# fbri_flight.net
KiCad netlist of a schematic drawn in EAGLE
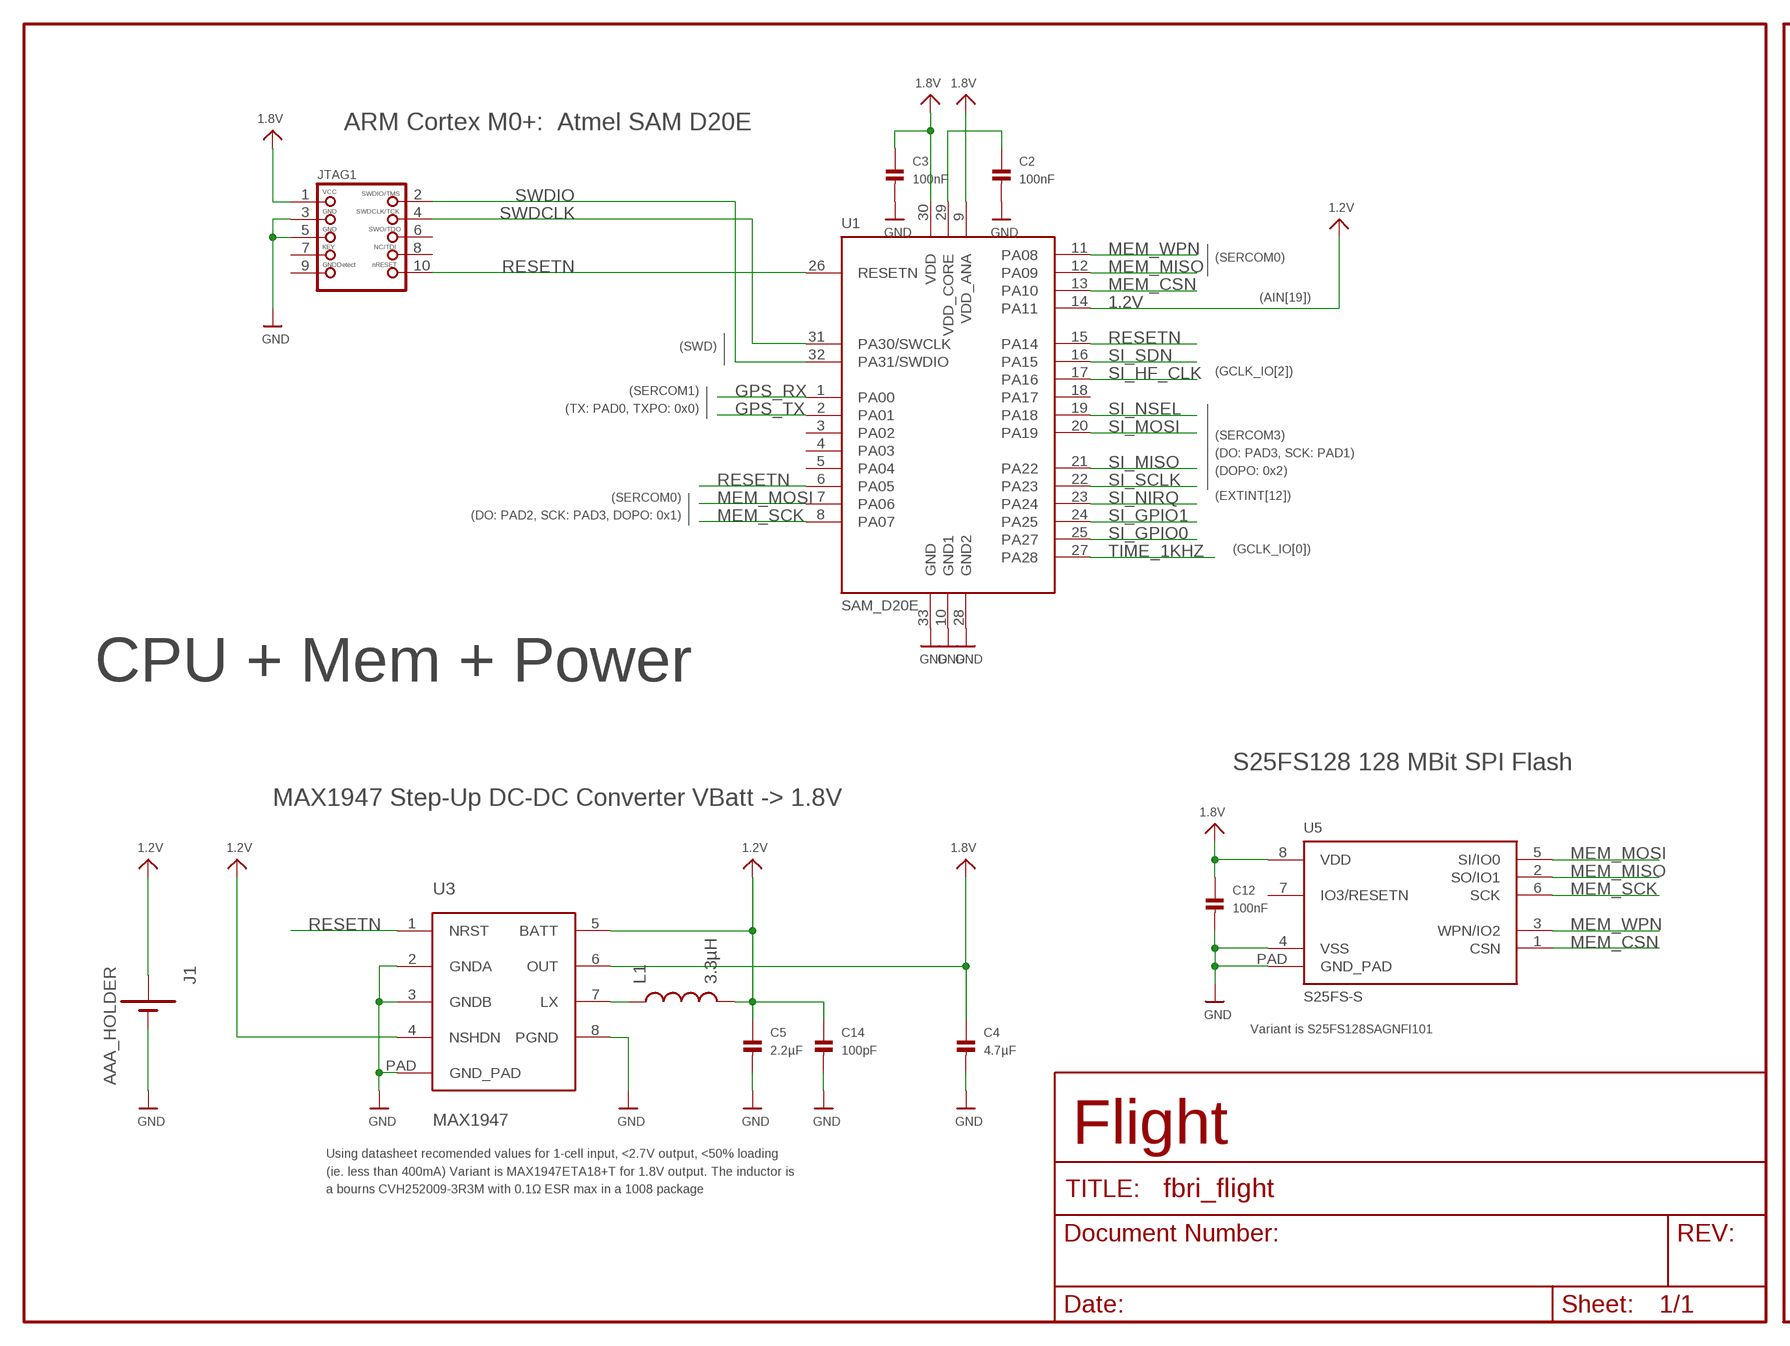
[diagram p0: schematic, sheet 1, part 1 of 2]
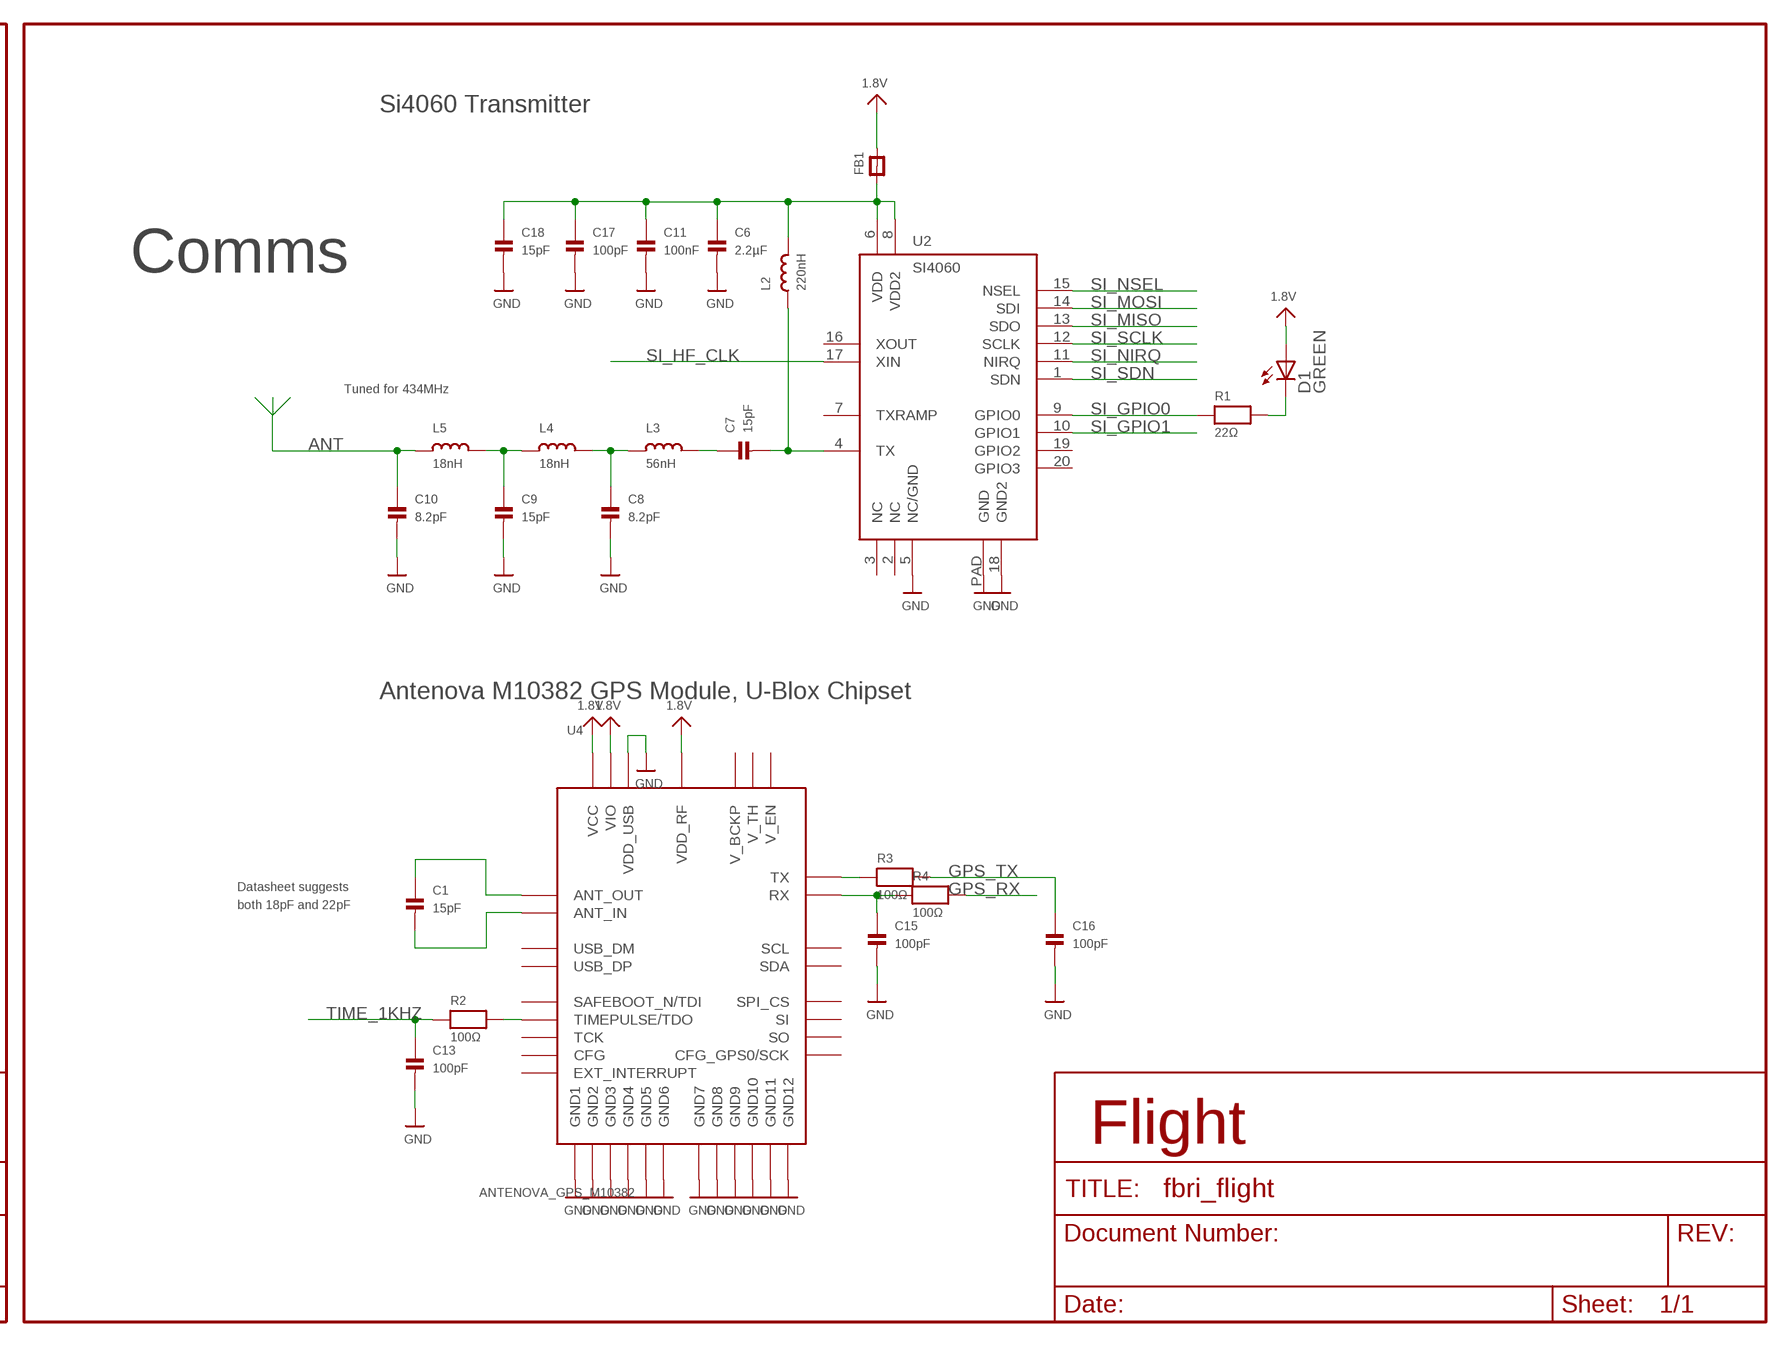
[diagram p1: schematic, sheet 1, part 2 of 2]

(export (version "E")
  (design (tool "Eeschema 10.0.6"))
  (components
    (comp (ref "C1")
      (value "15pF")
      (footprint "eagle-import:_0402")
      (libsource (lib "eagle-import") (part "CAP_CERAMIC_0402"))
    )
    (comp (ref "C2")
      (value "100nF")
      (footprint "eagle-import:_0402")
      (libsource (lib "eagle-import") (part "CAP_CERAMIC_0402"))
    )
    (comp (ref "C3")
      (value "100nF")
      (footprint "eagle-import:_0402")
      (libsource (lib "eagle-import") (part "CAP_CERAMIC_0402"))
    )
    (comp (ref "C4")
      (value "4.7µF")
      (footprint "eagle-import:_0402")
      (libsource (lib "eagle-import") (part "CAP_CERAMIC_0402"))
    )
    (comp (ref "C5")
      (value "2.2µF")
      (footprint "eagle-import:_0402")
      (libsource (lib "eagle-import") (part "CAP_CERAMIC_0402"))
    )
    (comp (ref "C6")
      (value "2.2µF")
      (footprint "eagle-import:_0402")
      (libsource (lib "eagle-import") (part "CAP_CERAMIC_0402"))
    )
    (comp (ref "C7")
      (value "15pF")
      (footprint "eagle-import:_0402")
      (libsource (lib "eagle-import") (part "CAP_CERAMIC_0402"))
    )
    (comp (ref "C8")
      (value "8.2pF")
      (footprint "eagle-import:_0402")
      (libsource (lib "eagle-import") (part "CAP_CERAMIC_0402"))
    )
    (comp (ref "C9")
      (value "15pF")
      (footprint "eagle-import:_0402")
      (libsource (lib "eagle-import") (part "CAP_CERAMIC_0402"))
    )
    (comp (ref "C10")
      (value "8.2pF")
      (footprint "eagle-import:_0402")
      (libsource (lib "eagle-import") (part "CAP_CERAMIC_0402"))
    )
    (comp (ref "C11")
      (value "100nF")
      (footprint "eagle-import:_0402")
      (libsource (lib "eagle-import") (part "CAP_CERAMIC_0402"))
    )
    (comp (ref "C12")
      (value "100nF")
      (footprint "eagle-import:_0402")
      (libsource (lib "eagle-import") (part "CAP_CERAMIC_0402"))
    )
    (comp (ref "C13")
      (value "100pF")
      (footprint "eagle-import:_0402")
      (libsource (lib "eagle-import") (part "CAP_CERAMIC_0402"))
    )
    (comp (ref "C14")
      (value "100pF")
      (footprint "eagle-import:_0402")
      (libsource (lib "eagle-import") (part "CAP_CERAMIC_0402"))
    )
    (comp (ref "C15")
      (value "100pF")
      (footprint "eagle-import:_0402")
      (libsource (lib "eagle-import") (part "CAP_CERAMIC_0402"))
    )
    (comp (ref "C16")
      (value "100pF")
      (footprint "eagle-import:_0402")
      (libsource (lib "eagle-import") (part "CAP_CERAMIC_0402"))
    )
    (comp (ref "C17")
      (value "100pF")
      (footprint "eagle-import:_0402")
      (libsource (lib "eagle-import") (part "CAP_CERAMIC_0402"))
    )
    (comp (ref "C18")
      (value "15pF")
      (footprint "eagle-import:_0402")
      (libsource (lib "eagle-import") (part "CAP_CERAMIC_0402"))
    )
    (comp (ref "D1")
      (value "GREEN")
      (footprint "eagle-import:CHIPLED_0603")
      (libsource (lib "eagle-import") (part "LEDCHIPLED_0603"))
    )
    (comp (ref "FB1")
      (value "FERRITE_0402")
      (footprint "eagle-import:_0402")
      (libsource (lib "eagle-import") (part "FERRITE_0402"))
    )
    (comp (ref "J1")
      (value "AAA_HOLDER")
      (footprint "eagle-import:AAA")
      (libsource (lib "eagle-import") (part "AAA_HOLDER"))
    )
    (comp (ref "JTAG1")
      (value "JTAG-CORTEXM3SMT")
      (footprint "eagle-import:2X05_1.27MM_SMT")
      (libsource (lib "eagle-import") (part "JTAG-CORTEXM3SMT"))
    )
    (comp (ref "L1")
      (value "3.3µH")
      (footprint "eagle-import:1007")
      (libsource (lib "eagle-import") (part "INDUCTOR1007"))
    )
    (comp (ref "L2")
      (value "220nH")
      (footprint "eagle-import:_0402")
      (libsource (lib "eagle-import") (part "INDUCTOR_0402"))
    )
    (comp (ref "L3")
      (value "56nH")
      (footprint "eagle-import:_0402")
      (libsource (lib "eagle-import") (part "INDUCTOR_0402"))
    )
    (comp (ref "L4")
      (value "18nH")
      (footprint "eagle-import:_0402")
      (libsource (lib "eagle-import") (part "INDUCTOR_0402"))
    )
    (comp (ref "L5")
      (value "18nH")
      (footprint "eagle-import:_0402")
      (libsource (lib "eagle-import") (part "INDUCTOR_0402"))
    )
    (comp (ref "R1")
      (value "22Ω")
      (footprint "eagle-import:_0402")
      (libsource (lib "eagle-import") (part "RESISTOR_0402"))
    )
    (comp (ref "R2")
      (value "100Ω")
      (footprint "eagle-import:_0402")
      (libsource (lib "eagle-import") (part "RESISTOR_0402"))
    )
    (comp (ref "R3")
      (value "100Ω")
      (footprint "eagle-import:_0402")
      (libsource (lib "eagle-import") (part "RESISTOR_0402"))
    )
    (comp (ref "R4")
      (value "100Ω")
      (footprint "eagle-import:_0402")
      (libsource (lib "eagle-import") (part "RESISTOR_0402"))
    )
    (comp (ref "U1")
      (value "SAM_D20E")
      (footprint "eagle-import:QFN32_5MM")
      (libsource (lib "eagle-import") (part "SAM_D20E"))
    )
    (comp (ref "U2")
      (value "SI4060")
      (footprint "eagle-import:QFN20")
      (libsource (lib "eagle-import") (part "SI4060"))
    )
    (comp (ref "U3")
      (value "MAX1947")
      (footprint "eagle-import:TDFN8")
      (libsource (lib "eagle-import") (part "MAX1947"))
    )
    (comp (ref "U4")
      (value "ANTENOVA_GPS_M10382")
      (footprint "eagle-import:ANTENOVA_GPS_M10382")
      (libsource (lib "eagle-import") (part "ANTENOVA_GPS_M10382"))
    )
    (comp (ref "U5")
      (value "S25FS-S")
      (footprint "eagle-import:WSON8")
      (libsource (lib "eagle-import") (part "S25FS-S"))
    )
  )
  (nets
    (net (code "1") (name "/ANT") (class "Default")
      (node (ref "C10") (pin "1") (pinfunction "P$1_1") (pintype "passive"))
      (node (ref "L5") (pin "1") (pinfunction "1_1") (pintype "passive"))
    )
    (net (code "2") (name "/GPS_RX") (class "Default")
      (node (ref "R4") (pin "2") (pinfunction "2_2") (pintype "passive"))
      (node (ref "U1") (pin "1") (pinfunction "PA00_1") (pintype "bidirectional"))
    )
    (net (code "3") (name "/GPS_TX") (class "Default")
      (node (ref "C16") (pin "1") (pinfunction "P$1_1") (pintype "passive"))
      (node (ref "R3") (pin "2") (pinfunction "2_2") (pintype "passive"))
      (node (ref "U1") (pin "2") (pinfunction "PA01_2") (pintype "bidirectional"))
    )
    (net (code "4") (name "/MEM_CSN") (class "Default")
      (node (ref "U1") (pin "13") (pinfunction "PA10_13") (pintype "bidirectional"))
      (node (ref "U5") (pin "1") (pinfunction "CSN_1") (pintype "input"))
    )
    (net (code "5") (name "/MEM_MISO") (class "Default")
      (node (ref "U1") (pin "12") (pinfunction "PA09_12") (pintype "bidirectional"))
      (node (ref "U5") (pin "2") (pinfunction "SO/IO1_2") (pintype "output"))
    )
    (net (code "6") (name "/MEM_MOSI") (class "Default")
      (node (ref "U1") (pin "7") (pinfunction "PA06_7") (pintype "bidirectional"))
      (node (ref "U5") (pin "5") (pinfunction "SI/IO0_5") (pintype "bidirectional"))
    )
    (net (code "7") (name "/MEM_SCK") (class "Default")
      (node (ref "U1") (pin "8") (pinfunction "PA07_8") (pintype "bidirectional"))
      (node (ref "U5") (pin "6") (pinfunction "SCK_6") (pintype "input"))
    )
    (net (code "8") (name "/MEM_WPN") (class "Default")
      (node (ref "U1") (pin "11") (pinfunction "PA08_11") (pintype "bidirectional"))
      (node (ref "U5") (pin "3") (pinfunction "WPN/IO2_3") (pintype "output"))
    )
    (net (code "9") (name "/RESETN") (class "Default")
      (node (ref "JTAG1") (pin "10") (pinfunction "10_10") (pintype "passive"))
      (node (ref "U1") (pin "15") (pinfunction "PA14_15") (pintype "bidirectional"))
      (node (ref "U1") (pin "26") (pinfunction "RESETN_26") (pintype "input"))
      (node (ref "U1") (pin "6") (pinfunction "PA05_6") (pintype "bidirectional"))
      (node (ref "U3") (pin "1") (pinfunction "NRST_1") (pintype "bidirectional"))
    )
    (net (code "10") (name "/SI_GPIO0") (class "Default")
      (node (ref "R1") (pin "1") (pinfunction "1_1") (pintype "passive"))
      (node (ref "U1") (pin "25") (pinfunction "PA27_25") (pintype "bidirectional"))
      (node (ref "U2") (pin "9") (pinfunction "GPIO0_9") (pintype "bidirectional"))
    )
    (net (code "11") (name "/SI_GPIO1") (class "Default")
      (node (ref "U1") (pin "24") (pinfunction "PA25_24") (pintype "bidirectional"))
      (node (ref "U2") (pin "10") (pinfunction "GPIO1_10") (pintype "bidirectional"))
    )
    (net (code "12") (name "/SI_HF_CLK") (class "Default")
      (node (ref "U1") (pin "17") (pinfunction "PA16_17") (pintype "bidirectional"))
      (node (ref "U2") (pin "17") (pinfunction "XIN_17") (pintype "input"))
    )
    (net (code "13") (name "/SI_MISO") (class "Default")
      (node (ref "U1") (pin "21") (pinfunction "PA22_21") (pintype "bidirectional"))
      (node (ref "U2") (pin "13") (pinfunction "SDO_13") (pintype "output"))
    )
    (net (code "14") (name "/SI_MOSI") (class "Default")
      (node (ref "U1") (pin "20") (pinfunction "PA19_20") (pintype "bidirectional"))
      (node (ref "U2") (pin "14") (pinfunction "SDI_14") (pintype "bidirectional"))
    )
    (net (code "15") (name "/SI_NIRQ") (class "Default")
      (node (ref "U1") (pin "23") (pinfunction "PA24_23") (pintype "bidirectional"))
      (node (ref "U2") (pin "11") (pinfunction "NIRQ_11") (pintype "output"))
    )
    (net (code "16") (name "/SI_NSEL") (class "Default")
      (node (ref "U1") (pin "19") (pinfunction "PA18_19") (pintype "bidirectional"))
      (node (ref "U2") (pin "15") (pinfunction "NSEL_15") (pintype "input"))
    )
    (net (code "17") (name "/SI_SCLK") (class "Default")
      (node (ref "U1") (pin "22") (pinfunction "PA23_22") (pintype "bidirectional"))
      (node (ref "U2") (pin "12") (pinfunction "SCLK_12") (pintype "input"))
    )
    (net (code "18") (name "/SI_SDN") (class "Default")
      (node (ref "U1") (pin "16") (pinfunction "PA15_16") (pintype "bidirectional"))
      (node (ref "U2") (pin "1") (pinfunction "SDN_1") (pintype "input"))
    )
    (net (code "19") (name "/SWDCLK") (class "Default")
      (node (ref "JTAG1") (pin "4") (pinfunction "4_4") (pintype "passive"))
      (node (ref "U1") (pin "31") (pinfunction "PA30/SWCLK_31") (pintype "bidirectional"))
    )
    (net (code "20") (name "/SWDIO") (class "Default")
      (node (ref "JTAG1") (pin "2") (pinfunction "2_2") (pintype "passive"))
      (node (ref "U1") (pin "32") (pinfunction "PA31/SWDIO_32") (pintype "bidirectional"))
    )
    (net (code "21") (name "/TIME_1KHZ") (class "Default")
      (node (ref "C13") (pin "1") (pinfunction "P$1_1") (pintype "passive"))
      (node (ref "R2") (pin "1") (pinfunction "1_1") (pintype "passive"))
      (node (ref "U1") (pin "27") (pinfunction "PA28_27") (pintype "bidirectional"))
    )
    (net (code "22") (name "1.2V") (class "Default")
      (node (ref "C14") (pin "1") (pinfunction "P$1_1") (pintype "passive"))
      (node (ref "C5") (pin "1") (pinfunction "P$1_1") (pintype "passive"))
      (node (ref "J1") (pin "+2") (pinfunction "+_+2") (pintype "power_in"))
      (node (ref "L1") (pin "2") (pinfunction "2_2") (pintype "passive"))
      (node (ref "U1") (pin "14") (pinfunction "PA11_14") (pintype "bidirectional"))
      (node (ref "U3") (pin "4") (pinfunction "NSHDN_4") (pintype "bidirectional"))
      (node (ref "U3") (pin "5") (pinfunction "BATT_5") (pintype "bidirectional"))
    )
    (net (code "23") (name "1.8V") (class "Default")
      (node (ref "C12") (pin "1") (pinfunction "P$1_1") (pintype "passive"))
      (node (ref "C3") (pin "1") (pinfunction "P$1_1") (pintype "passive"))
      (node (ref "C4") (pin "1") (pinfunction "P$1_1") (pintype "passive"))
      (node (ref "D1") (pin "A") (pinfunction "A_A") (pintype "passive"))
      (node (ref "FB1") (pin "2") (pinfunction "P$2_2") (pintype "passive"))
      (node (ref "JTAG1") (pin "1") (pinfunction "1_1") (pintype "passive"))
      (node (ref "U1") (pin "30") (pinfunction "VDD_30") (pintype "power_in"))
      (node (ref "U1") (pin "9") (pinfunction "VDD_ANA_9") (pintype "power_in"))
      (node (ref "U3") (pin "6") (pinfunction "OUT_6") (pintype "bidirectional"))
      (node (ref "U4") (pin "25_VDD_RF") (pinfunction "VDD_RF_25_VDD_RF") (pintype "power_in"))
      (node (ref "U4") (pin "27_VCC") (pinfunction "VCC_27_VCC") (pintype "power_in"))
      (node (ref "U4") (pin "5_VIO") (pinfunction "VIO_5_VIO") (pintype "bidirectional"))
      (node (ref "U5") (pin "8") (pinfunction "VDD_8") (pintype "power_in"))
    )
    (net (code "24") (name "GND") (class "Default")
      (node (ref "C10") (pin "2") (pinfunction "P$2_2") (pintype "passive"))
      (node (ref "C11") (pin "2") (pinfunction "P$2_2") (pintype "passive"))
      (node (ref "C12") (pin "2") (pinfunction "P$2_2") (pintype "passive"))
      (node (ref "C13") (pin "2") (pinfunction "P$2_2") (pintype "passive"))
      (node (ref "C14") (pin "2") (pinfunction "P$2_2") (pintype "passive"))
      (node (ref "C15") (pin "2") (pinfunction "P$2_2") (pintype "passive"))
      (node (ref "C16") (pin "2") (pinfunction "P$2_2") (pintype "passive"))
      (node (ref "C17") (pin "2") (pinfunction "P$2_2") (pintype "passive"))
      (node (ref "C18") (pin "2") (pinfunction "P$2_2") (pintype "passive"))
      (node (ref "C2") (pin "2") (pinfunction "P$2_2") (pintype "passive"))
      (node (ref "C3") (pin "2") (pinfunction "P$2_2") (pintype "passive"))
      (node (ref "C4") (pin "2") (pinfunction "P$2_2") (pintype "passive"))
      (node (ref "C5") (pin "2") (pinfunction "P$2_2") (pintype "passive"))
      (node (ref "C6") (pin "2") (pinfunction "P$2_2") (pintype "passive"))
      (node (ref "C8") (pin "2") (pinfunction "P$2_2") (pintype "passive"))
      (node (ref "C9") (pin "2") (pinfunction "P$2_2") (pintype "passive"))
      (node (ref "J1") (pin "-1") (pinfunction "-_-1") (pintype "power_in"))
      (node (ref "J1") (pin "-2") (pinfunction "-_-2") (pintype "power_in"))
      (node (ref "JTAG1") (pin "3") (pinfunction "3_3") (pintype "passive"))
      (node (ref "JTAG1") (pin "5") (pinfunction "5_5") (pintype "passive"))
      (node (ref "U1") (pin "10") (pinfunction "GND1_10") (pintype "power_in"))
      (node (ref "U1") (pin "28") (pinfunction "GND2_28") (pintype "power_in"))
      (node (ref "U1") (pin "33") (pinfunction "GND_33") (pintype "power_in"))
      (node (ref "U2") (pin "18") (pinfunction "GND2_18") (pintype "power_in"))
      (node (ref "U2") (pin "5") (pinfunction "NC/GND_5") (pintype "bidirectional"))
      (node (ref "U2") (pin "PAD") (pinfunction "GND_PAD") (pintype "power_in"))
      (node (ref "U3") (pin "2") (pinfunction "GNDA_2") (pintype "bidirectional"))
      (node (ref "U3") (pin "3") (pinfunction "GNDB_3") (pintype "bidirectional"))
      (node (ref "U3") (pin "8") (pinfunction "PGND_8") (pintype "bidirectional"))
      (node (ref "U3") (pin "PAD") (pinfunction "GND_PAD_PAD") (pintype "bidirectional"))
      (node (ref "U4") (pin "14_GND") (pinfunction "GND3_14_GND") (pintype "power_in"))
      (node (ref "U4") (pin "17_GND") (pinfunction "GND4_17_GND") (pintype "power_in"))
      (node (ref "U4") (pin "21_GND") (pinfunction "GND5_21_GND") (pintype "bidirectional"))
      (node (ref "U4") (pin "24_GND") (pinfunction "GND6_24_GND") (pintype "bidirectional"))
      (node (ref "U4") (pin "26_GND") (pinfunction "GND7_26_GND") (pintype "power_in"))
      (node (ref "U4") (pin "28_GND") (pinfunction "GND8_28_GND") (pintype "power_in"))
      (node (ref "U4") (pin "2_GND") (pinfunction "GND1_2_GND") (pintype "power_in"))
      (node (ref "U4") (pin "32_VDD_USB") (pinfunction "VDD_USB_32_VDD_USB") (pintype "bidirectional"))
      (node (ref "U4") (pin "33_GND") (pinfunction "GND9_33_GND") (pintype "power_in"))
      (node (ref "U4") (pin "34_GND") (pinfunction "GND10_34_GND") (pintype "power_in"))
      (node (ref "U4") (pin "35_GND") (pinfunction "GND11_35_GND") (pintype "bidirectional"))
      (node (ref "U4") (pin "36_GND") (pinfunction "GND12_36_GND") (pintype "bidirectional"))
      (node (ref "U4") (pin "4_GND") (pinfunction "GND2_4_GND") (pintype "power_in"))
      (node (ref "U5") (pin "4") (pinfunction "VSS_4") (pintype "power_in"))
      (node (ref "U5") (pin "PAD") (pinfunction "GND_PAD_PAD") (pintype "power_in"))
    )
    (net (code "25") (name "Net-(C1-P$1)") (class "Default")
      (node (ref "C1") (pin "1") (pinfunction "P$1_1") (pintype "passive"))
      (node (ref "U4") (pin "3_ANT_OUT") (pinfunction "ANT_OUT_3_ANT_OUT") (pintype "output"))
    )
    (net (code "26") (name "Net-(C1-P$2)") (class "Default")
      (node (ref "C1") (pin "2") (pinfunction "P$2_2") (pintype "passive"))
      (node (ref "U4") (pin "1_ANT_IN") (pinfunction "ANT_IN_1_ANT_IN") (pintype "input"))
    )
    (net (code "27") (name "Net-(C2-P$1)") (class "Default")
      (node (ref "C2") (pin "1") (pinfunction "P$1_1") (pintype "passive"))
      (node (ref "U1") (pin "29") (pinfunction "VDD_CORE_29") (pintype "power_in"))
    )
    (net (code "28") (name "Net-(C7-P$1)") (class "Default")
      (node (ref "C7") (pin "1") (pinfunction "P$1_1") (pintype "passive"))
      (node (ref "L3") (pin "2") (pinfunction "2_2") (pintype "passive"))
    )
    (net (code "29") (name "Net-(C7-P$2)") (class "Default")
      (node (ref "C7") (pin "2") (pinfunction "P$2_2") (pintype "passive"))
      (node (ref "L2") (pin "1") (pinfunction "1_1") (pintype "passive"))
      (node (ref "U2") (pin "4") (pinfunction "TX_4") (pintype "output"))
    )
    (net (code "30") (name "Net-(C8-P$1)") (class "Default")
      (node (ref "C8") (pin "1") (pinfunction "P$1_1") (pintype "passive"))
      (node (ref "L3") (pin "1") (pinfunction "1_1") (pintype "passive"))
      (node (ref "L4") (pin "2") (pinfunction "2_2") (pintype "passive"))
    )
    (net (code "31") (name "Net-(C9-P$1)") (class "Default")
      (node (ref "C9") (pin "1") (pinfunction "P$1_1") (pintype "passive"))
      (node (ref "L4") (pin "1") (pinfunction "1_1") (pintype "passive"))
      (node (ref "L5") (pin "2") (pinfunction "2_2") (pintype "passive"))
    )
    (net (code "32") (name "Net-(C11-P$1)") (class "Default")
      (node (ref "C11") (pin "1") (pinfunction "P$1_1") (pintype "passive"))
      (node (ref "C17") (pin "1") (pinfunction "P$1_1") (pintype "passive"))
      (node (ref "C18") (pin "1") (pinfunction "P$1_1") (pintype "passive"))
      (node (ref "C6") (pin "1") (pinfunction "P$1_1") (pintype "passive"))
      (node (ref "FB1") (pin "1") (pinfunction "P$1_1") (pintype "passive"))
      (node (ref "L2") (pin "2") (pinfunction "2_2") (pintype "passive"))
      (node (ref "U2") (pin "6") (pinfunction "VDD_6") (pintype "power_in"))
      (node (ref "U2") (pin "8") (pinfunction "VDD2_8") (pintype "power_in"))
    )
    (net (code "33") (name "Net-(C15-P$1)") (class "Default")
      (node (ref "C15") (pin "1") (pinfunction "P$1_1") (pintype "passive"))
      (node (ref "R4") (pin "1") (pinfunction "1_1") (pintype "passive"))
      (node (ref "U4") (pin "13_RX") (pinfunction "RX_13_RX") (pintype "bidirectional"))
    )
    (net (code "34") (name "Net-(D1-PadC)") (class "Default")
      (node (ref "D1") (pin "C") (pinfunction "C_C") (pintype "passive"))
      (node (ref "R1") (pin "2") (pinfunction "2_2") (pintype "passive"))
    )
    (net (code "35") (name "Net-(U3-LX)") (class "Default")
      (node (ref "L1") (pin "1") (pinfunction "1_1") (pintype "passive"))
      (node (ref "U3") (pin "7") (pinfunction "LX_7") (pintype "bidirectional"))
    )
    (net (code "36") (name "Net-(U4-TIMEPULSE{slash}TDO)") (class "Default")
      (node (ref "R2") (pin "2") (pinfunction "2_2") (pintype "passive"))
      (node (ref "U4") (pin "23_TIMEPULSE/TDO") (pinfunction "TIMEPULSE/TDO_23_TIMEPULSE/TDO") (pintype "bidirectional"))
    )
    (net (code "37") (name "Net-(U4-TX)") (class "Default")
      (node (ref "R3") (pin "1") (pinfunction "1_1") (pintype "passive"))
      (node (ref "U4") (pin "11_TX") (pinfunction "TX_11_TX") (pintype "bidirectional"))
    )
    (net (code "38") (name "unconnected-(JTAG1-Pad6)") (class "Default")
      (node (ref "JTAG1") (pin "6") (pinfunction "6_6") (pintype "passive"))
    )
    (net (code "39") (name "unconnected-(JTAG1-Pad7)") (class "Default")
      (node (ref "JTAG1") (pin "7") (pinfunction "7_7") (pintype "passive"))
    )
    (net (code "40") (name "unconnected-(JTAG1-Pad8)") (class "Default")
      (node (ref "JTAG1") (pin "8") (pinfunction "8_8") (pintype "passive"))
    )
    (net (code "41") (name "unconnected-(JTAG1-Pad9)") (class "Default")
      (node (ref "JTAG1") (pin "9") (pinfunction "9_9") (pintype "passive"))
    )
    (net (code "42") (name "unconnected-(U1-PA02-Pad3)") (class "Default")
      (node (ref "U1") (pin "3") (pinfunction "PA02_3") (pintype "bidirectional"))
    )
    (net (code "43") (name "unconnected-(U1-PA03-Pad4)") (class "Default")
      (node (ref "U1") (pin "4") (pinfunction "PA03_4") (pintype "bidirectional"))
    )
    (net (code "44") (name "unconnected-(U1-PA04-Pad5)") (class "Default")
      (node (ref "U1") (pin "5") (pinfunction "PA04_5") (pintype "bidirectional"))
    )
    (net (code "45") (name "unconnected-(U1-PA17-Pad18)") (class "Default")
      (node (ref "U1") (pin "18") (pinfunction "PA17_18") (pintype "bidirectional"))
    )
    (net (code "46") (name "unconnected-(U2-GPIO2-Pad19)") (class "Default")
      (node (ref "U2") (pin "19") (pinfunction "GPIO2_19") (pintype "bidirectional"))
    )
    (net (code "47") (name "unconnected-(U2-GPIO3-Pad20)") (class "Default")
      (node (ref "U2") (pin "20") (pinfunction "GPIO3_20") (pintype "bidirectional"))
    )
    (net (code "48") (name "unconnected-(U2-NC-Pad2)") (class "Default")
      (node (ref "U2") (pin "2") (pinfunction "NC_2") (pintype "no_connect"))
    )
    (net (code "49") (name "unconnected-(U2-NC -Pad3)") (class "Default")
      (node (ref "U2") (pin "3") (pinfunction "NC _3") (pintype "no_connect"))
    )
    (net (code "50") (name "unconnected-(U2-TXRAMP-Pad7)") (class "Default")
      (node (ref "U2") (pin "7") (pinfunction "TXRAMP_7") (pintype "bidirectional"))
    )
    (net (code "51") (name "unconnected-(U2-XOUT-Pad16)") (class "Default")
      (node (ref "U2") (pin "16") (pinfunction "XOUT_16") (pintype "output"))
    )
    (net (code "52") (name "unconnected-(U4-CFG-Pad31_CFG)") (class "Default")
      (node (ref "U4") (pin "31_CFG") (pinfunction "CFG_31_CFG") (pintype "bidirectional"))
    )
    (net (code "53") (name "unconnected-(U4-CFG_GPS0{slash}SCK-Pad9_CFG_GPS0_SCK)") (class "Default")
      (node (ref "U4") (pin "9_CFG_GPS0_SCK") (pinfunction "CFG_GPS0/SCK_9_CFG_GPS0_SCK") (pintype "bidirectional"))
    )
    (net (code "54") (name "unconnected-(U4-EXT_INTERRUPT-Pad29_EXT_INTERRUPT)") (class "Default")
      (node (ref "U4") (pin "29_EXT_INTERRUPT") (pinfunction "EXT_INTERRUPT_29_EXT_INTERRUPT") (pintype "bidirectional"))
    )
    (net (code "55") (name "unconnected-(U4-SAFEBOOT_N{slash}TDI-Pad20_SAFEBOOT_N{slash}TDI)") (class "Default")
      (node (ref "U4") (pin "20_SAFEBOOT_N/TDI") (pinfunction "SAFEBOOT_N/TDI_20_SAFEBOOT_N/TDI") (pintype "bidirectional"))
    )
    (net (code "56") (name "unconnected-(U4-SCL-Pad19_SCL)") (class "Default")
      (node (ref "U4") (pin "19_SCL") (pinfunction "SCL_19_SCL") (pintype "bidirectional"))
    )
    (net (code "57") (name "unconnected-(U4-SDA-Pad18_SDA)") (class "Default")
      (node (ref "U4") (pin "18_SDA") (pinfunction "SDA_18_SDA") (pintype "bidirectional"))
    )
    (net (code "58") (name "unconnected-(U4-SI-Pad16_SI)") (class "Default")
      (node (ref "U4") (pin "16_SI") (pinfunction "SI_16_SI") (pintype "bidirectional"))
    )
    (net (code "59") (name "unconnected-(U4-SO-Pad8_SO)") (class "Default")
      (node (ref "U4") (pin "8_SO") (pinfunction "SO_8_SO") (pintype "bidirectional"))
    )
    (net (code "60") (name "unconnected-(U4-SPI_CS-Pad10_SPI_SELECT)") (class "Default")
      (node (ref "U4") (pin "10_SPI_SELECT") (pinfunction "SPI_CS_10_SPI_SELECT") (pintype "bidirectional"))
    )
    (net (code "61") (name "unconnected-(U4-TCK-Pad22_TCK)") (class "Default")
      (node (ref "U4") (pin "22_TCK") (pinfunction "TCK_22_TCK") (pintype "bidirectional"))
    )
    (net (code "62") (name "unconnected-(U4-USB_DM-Pad7_USB_DM)") (class "Default")
      (node (ref "U4") (pin "7_USB_DM") (pinfunction "USB_DM_7_USB_DM") (pintype "bidirectional"))
    )
    (net (code "63") (name "unconnected-(U4-USB_DP-Pad6_USB_DP)") (class "Default")
      (node (ref "U4") (pin "6_USB_DP") (pinfunction "USB_DP_6_USB_DP") (pintype "bidirectional"))
    )
    (net (code "64") (name "unconnected-(U4-V_BCKP-Pad15_V_BCKUP)") (class "Default")
      (node (ref "U4") (pin "15_V_BCKUP") (pinfunction "V_BCKP_15_V_BCKUP") (pintype "bidirectional"))
    )
    (net (code "65") (name "unconnected-(U4-V_EN-Pad30_V_EN)") (class "Default")
      (node (ref "U4") (pin "30_V_EN") (pinfunction "V_EN_30_V_EN") (pintype "bidirectional"))
    )
    (net (code "66") (name "unconnected-(U4-V_TH-Pad12_V_TH)") (class "Default")
      (node (ref "U4") (pin "12_V_TH") (pinfunction "V_TH_12_V_TH") (pintype "bidirectional"))
    )
    (net (code "67") (name "unconnected-(U5-IO3{slash}RESETN-Pad7)") (class "Default")
      (node (ref "U5") (pin "7") (pinfunction "IO3/RESETN_7") (pintype "output"))
    )
  )
)
